# FULL_CB_80_Pin_REV_C.net
KiCad netlist of a schematic drawn in Altium Designer
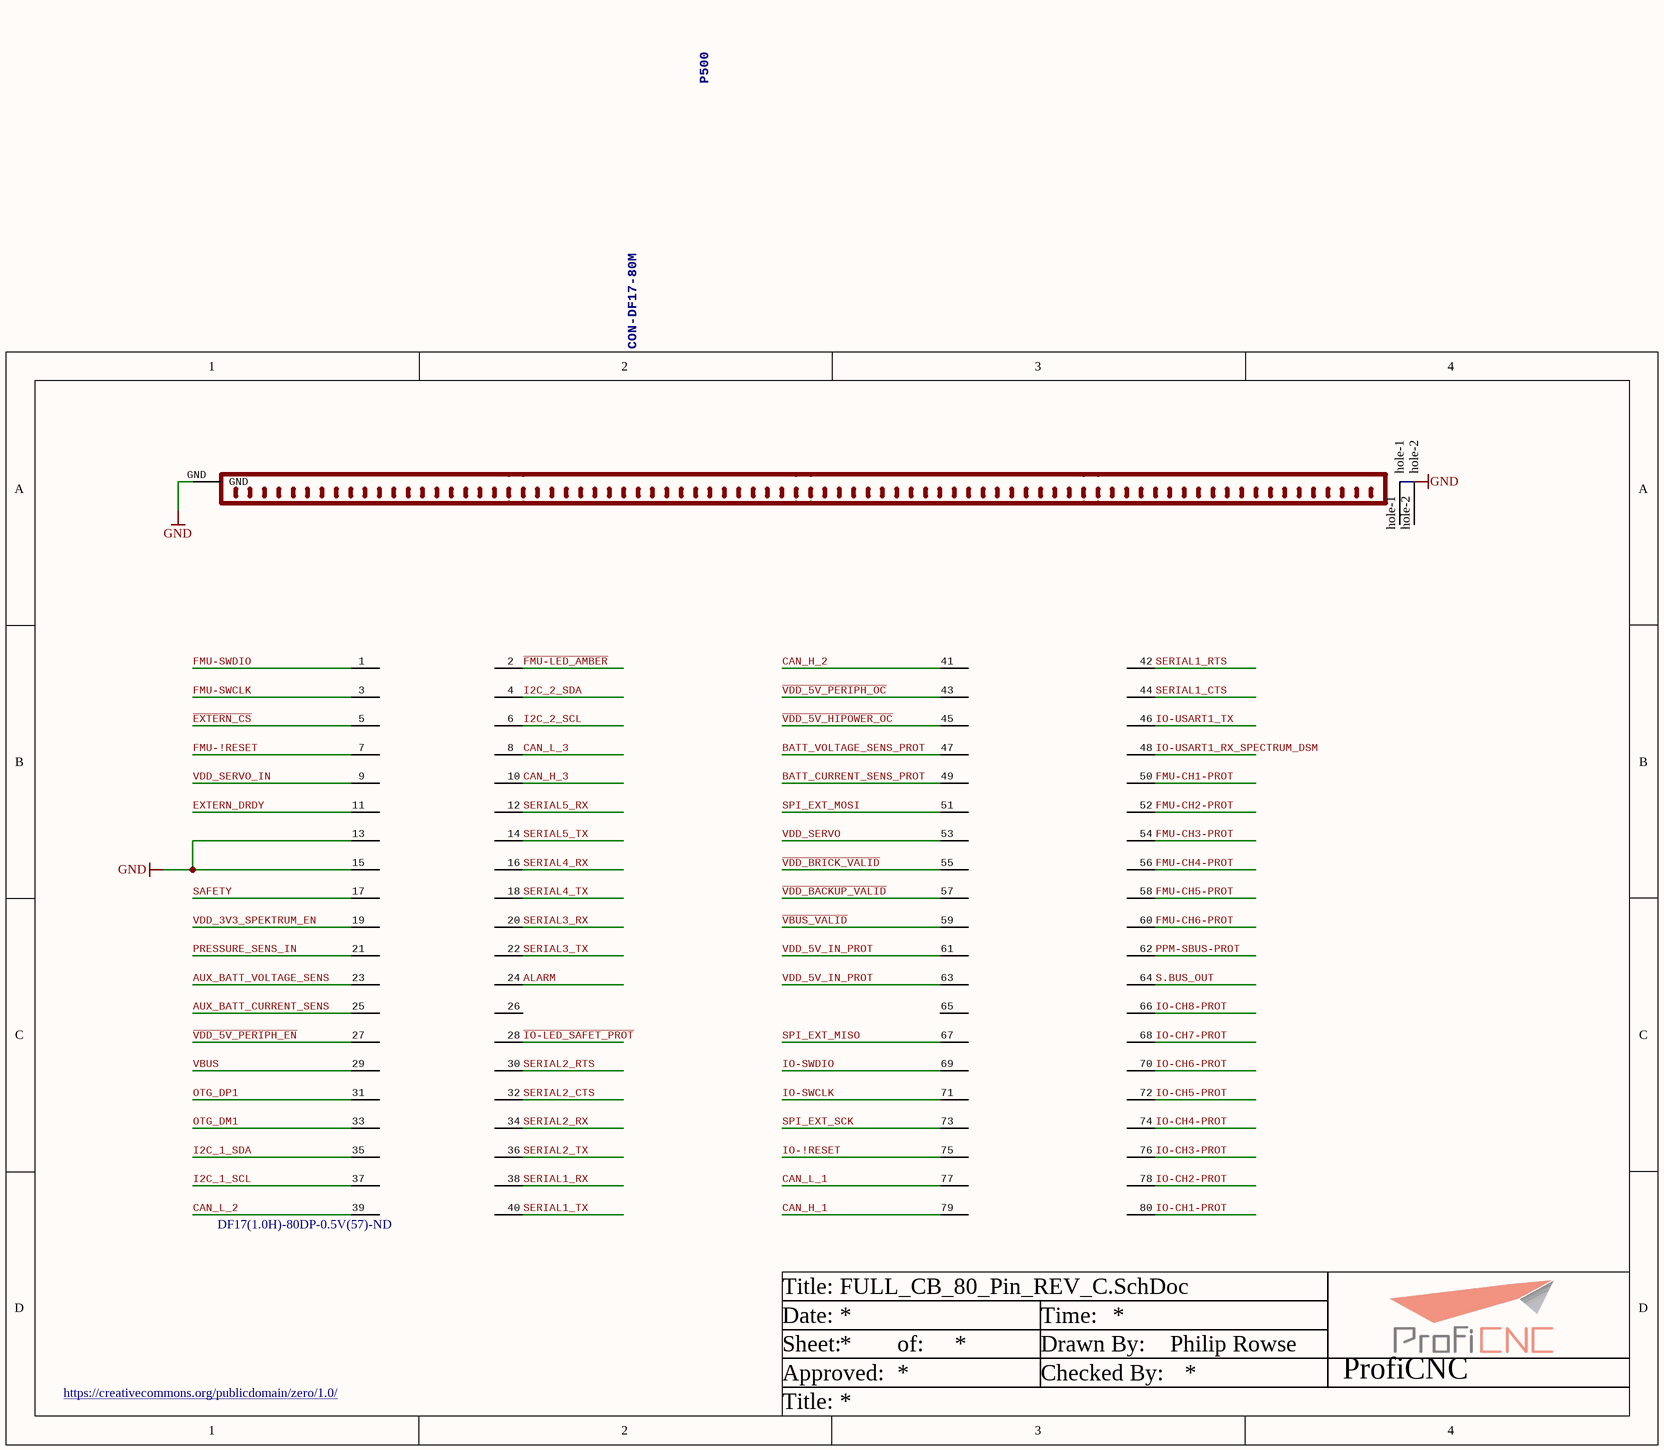
[diagram p0: FULL_CB_80_Pin_REV_C.SchDoc]

(export (version "E")
  (design (tool "Eeschema 10.0.6"))
  (components
    (comp (ref "P500")
      (value "CON-DF17-80M")
      (description "Connector, Header, 80Pos, .5MM, DUAL, SMD, Au")
      (fields (field (name "SUPPLIER PART NUMBER 1") "DF17(1.0H)-80DP-0.5V(57)-ND"))
      (libsource (lib "CB_REV_C") (part "CON-DF17-80M"))
    )
  )
  (nets
    (net (code "1") (name "/ALARM") (class "Default")
      (node (ref "P500") (pin "24") (pinfunction "24_24") (pintype "passive"))
    )
    (net (code "2") (name "/AUX_BATT_CURRENT_SENS") (class "Default")
      (node (ref "P500") (pin "25") (pinfunction "25_25") (pintype "passive"))
    )
    (net (code "3") (name "/AUX_BATT_VOLTAGE_SENS") (class "Default")
      (node (ref "P500") (pin "23") (pinfunction "23_23") (pintype "passive"))
    )
    (net (code "4") (name "/BATT_CURRENT_SENS_PROT") (class "Default")
      (node (ref "P500") (pin "49") (pinfunction "49_49") (pintype "passive"))
    )
    (net (code "5") (name "/BATT_VOLTAGE_SENS_PROT") (class "Default")
      (node (ref "P500") (pin "47") (pinfunction "47_47") (pintype "passive"))
    )
    (net (code "6") (name "/CAN_H_1") (class "Default")
      (node (ref "P500") (pin "79") (pinfunction "79_79") (pintype "passive"))
    )
    (net (code "7") (name "/CAN_H_2") (class "Default")
      (node (ref "P500") (pin "41") (pinfunction "41_41") (pintype "passive"))
    )
    (net (code "8") (name "/CAN_H_3") (class "Default")
      (node (ref "P500") (pin "10") (pinfunction "10_10") (pintype "passive"))
    )
    (net (code "9") (name "/CAN_L_1") (class "Default")
      (node (ref "P500") (pin "77") (pinfunction "77_77") (pintype "passive"))
    )
    (net (code "10") (name "/CAN_L_2") (class "Default")
      (node (ref "P500") (pin "39") (pinfunction "39_39") (pintype "passive"))
    )
    (net (code "11") (name "/CAN_L_3") (class "Default")
      (node (ref "P500") (pin "8") (pinfunction "8_8") (pintype "passive"))
    )
    (net (code "12") (name "/EXTERN_DRDY") (class "Default")
      (node (ref "P500") (pin "11") (pinfunction "11_11") (pintype "passive"))
    )
    (net (code "13") (name "/FMU-!RESET") (class "Default")
      (node (ref "P500") (pin "7") (pinfunction "7_7") (pintype "passive"))
    )
    (net (code "14") (name "/FMU-CH1-PROT") (class "Default")
      (node (ref "P500") (pin "50") (pinfunction "50_50") (pintype "passive"))
    )
    (net (code "15") (name "/FMU-CH2-PROT") (class "Default")
      (node (ref "P500") (pin "52") (pinfunction "52_52") (pintype "passive"))
    )
    (net (code "16") (name "/FMU-CH3-PROT") (class "Default")
      (node (ref "P500") (pin "54") (pinfunction "54_54") (pintype "passive"))
    )
    (net (code "17") (name "/FMU-CH4-PROT") (class "Default")
      (node (ref "P500") (pin "56") (pinfunction "56_56") (pintype "passive"))
    )
    (net (code "18") (name "/FMU-CH5-PROT") (class "Default")
      (node (ref "P500") (pin "58") (pinfunction "58_58") (pintype "passive"))
    )
    (net (code "19") (name "/FMU-CH6-PROT") (class "Default")
      (node (ref "P500") (pin "60") (pinfunction "60_60") (pintype "passive"))
    )
    (net (code "20") (name "/FMU-SWCLK") (class "Default")
      (node (ref "P500") (pin "3") (pinfunction "3_3") (pintype "passive"))
    )
    (net (code "21") (name "/FMU-SWDIO") (class "Default")
      (node (ref "P500") (pin "1") (pinfunction "1_1") (pintype "passive"))
    )
    (net (code "22") (name "/I2C_1_SCL") (class "Default")
      (node (ref "P500") (pin "37") (pinfunction "37_37") (pintype "passive"))
    )
    (net (code "23") (name "/I2C_1_SDA") (class "Default")
      (node (ref "P500") (pin "35") (pinfunction "35_35") (pintype "passive"))
    )
    (net (code "24") (name "/I2C_2_SCL") (class "Default")
      (node (ref "P500") (pin "6") (pinfunction "6_6") (pintype "passive"))
    )
    (net (code "25") (name "/I2C_2_SDA") (class "Default")
      (node (ref "P500") (pin "4") (pinfunction "4_4") (pintype "passive"))
    )
    (net (code "26") (name "/IO-!RESET") (class "Default")
      (node (ref "P500") (pin "75") (pinfunction "75_75") (pintype "passive"))
    )
    (net (code "27") (name "/IO-CH1-PROT") (class "Default")
      (node (ref "P500") (pin "80") (pinfunction "80_80") (pintype "passive"))
    )
    (net (code "28") (name "/IO-CH2-PROT") (class "Default")
      (node (ref "P500") (pin "78") (pinfunction "78_78") (pintype "passive"))
    )
    (net (code "29") (name "/IO-CH3-PROT") (class "Default")
      (node (ref "P500") (pin "76") (pinfunction "76_76") (pintype "passive"))
    )
    (net (code "30") (name "/IO-CH4-PROT") (class "Default")
      (node (ref "P500") (pin "74") (pinfunction "74_74") (pintype "passive"))
    )
    (net (code "31") (name "/IO-CH5-PROT") (class "Default")
      (node (ref "P500") (pin "72") (pinfunction "72_72") (pintype "passive"))
    )
    (net (code "32") (name "/IO-CH6-PROT") (class "Default")
      (node (ref "P500") (pin "70") (pinfunction "70_70") (pintype "passive"))
    )
    (net (code "33") (name "/IO-CH7-PROT") (class "Default")
      (node (ref "P500") (pin "68") (pinfunction "68_68") (pintype "passive"))
    )
    (net (code "34") (name "/IO-CH8-PROT") (class "Default")
      (node (ref "P500") (pin "66") (pinfunction "66_66") (pintype "passive"))
    )
    (net (code "35") (name "/IO-SWCLK") (class "Default")
      (node (ref "P500") (pin "71") (pinfunction "71_71") (pintype "passive"))
    )
    (net (code "36") (name "/IO-SWDIO") (class "Default")
      (node (ref "P500") (pin "69") (pinfunction "69_69") (pintype "passive"))
    )
    (net (code "37") (name "/IO-USART1_RX_SPECTRUM_DSM") (class "Default")
      (node (ref "P500") (pin "48") (pinfunction "48_48") (pintype "passive"))
    )
    (net (code "38") (name "/IO-USART1_TX") (class "Default")
      (node (ref "P500") (pin "46") (pinfunction "46_46") (pintype "passive"))
    )
    (net (code "39") (name "/OTG_DM1") (class "Default")
      (node (ref "P500") (pin "33") (pinfunction "33_33") (pintype "passive"))
    )
    (net (code "40") (name "/OTG_DP1") (class "Default")
      (node (ref "P500") (pin "31") (pinfunction "31_31") (pintype "passive"))
    )
    (net (code "41") (name "/PPM-SBUS-PROT") (class "Default")
      (node (ref "P500") (pin "62") (pinfunction "62_62") (pintype "passive"))
    )
    (net (code "42") (name "/PRESSURE_SENS_IN") (class "Default")
      (node (ref "P500") (pin "21") (pinfunction "21_21") (pintype "passive"))
    )
    (net (code "43") (name "/S.BUS_OUT") (class "Default")
      (node (ref "P500") (pin "64") (pinfunction "64_64") (pintype "passive"))
    )
    (net (code "44") (name "/SAFETY") (class "Default")
      (node (ref "P500") (pin "17") (pinfunction "17_17") (pintype "passive"))
    )
    (net (code "45") (name "/SERIAL1_CTS") (class "Default")
      (node (ref "P500") (pin "44") (pinfunction "44_44") (pintype "passive"))
    )
    (net (code "46") (name "/SERIAL1_RTS") (class "Default")
      (node (ref "P500") (pin "42") (pinfunction "42_42") (pintype "passive"))
    )
    (net (code "47") (name "/SERIAL1_RX") (class "Default")
      (node (ref "P500") (pin "38") (pinfunction "38_38") (pintype "passive"))
    )
    (net (code "48") (name "/SERIAL1_TX") (class "Default")
      (node (ref "P500") (pin "40") (pinfunction "40_40") (pintype "passive"))
    )
    (net (code "49") (name "/SERIAL2_CTS") (class "Default")
      (node (ref "P500") (pin "32") (pinfunction "32_32") (pintype "passive"))
    )
    (net (code "50") (name "/SERIAL2_RTS") (class "Default")
      (node (ref "P500") (pin "30") (pinfunction "30_30") (pintype "passive"))
    )
    (net (code "51") (name "/SERIAL2_RX") (class "Default")
      (node (ref "P500") (pin "34") (pinfunction "34_34") (pintype "passive"))
    )
    (net (code "52") (name "/SERIAL2_TX") (class "Default")
      (node (ref "P500") (pin "36") (pinfunction "36_36") (pintype "passive"))
    )
    (net (code "53") (name "/SERIAL3_RX") (class "Default")
      (node (ref "P500") (pin "20") (pinfunction "20_20") (pintype "passive"))
    )
    (net (code "54") (name "/SERIAL3_TX") (class "Default")
      (node (ref "P500") (pin "22") (pinfunction "22_22") (pintype "passive"))
    )
    (net (code "55") (name "/SERIAL4_RX") (class "Default")
      (node (ref "P500") (pin "16") (pinfunction "16_16") (pintype "passive"))
    )
    (net (code "56") (name "/SERIAL4_TX") (class "Default")
      (node (ref "P500") (pin "18") (pinfunction "18_18") (pintype "passive"))
    )
    (net (code "57") (name "/SERIAL5_RX") (class "Default")
      (node (ref "P500") (pin "12") (pinfunction "12_12") (pintype "passive"))
    )
    (net (code "58") (name "/SERIAL5_TX") (class "Default")
      (node (ref "P500") (pin "14") (pinfunction "14_14") (pintype "passive"))
    )
    (net (code "59") (name "/SPI_EXT_MISO") (class "Default")
      (node (ref "P500") (pin "67") (pinfunction "67_67") (pintype "passive"))
    )
    (net (code "60") (name "/SPI_EXT_MOSI") (class "Default")
      (node (ref "P500") (pin "51") (pinfunction "51_51") (pintype "passive"))
    )
    (net (code "61") (name "/SPI_EXT_SCK") (class "Default")
      (node (ref "P500") (pin "73") (pinfunction "73_73") (pintype "passive"))
    )
    (net (code "62") (name "/VBUS") (class "Default")
      (node (ref "P500") (pin "29") (pinfunction "29_29") (pintype "passive"))
    )
    (net (code "63") (name "/VDD_3V3_SPEKTRUM_EN") (class "Default")
      (node (ref "P500") (pin "19") (pinfunction "19_19") (pintype "passive"))
    )
    (net (code "64") (name "/VDD_5V_IN_PROT") (class "Default")
      (node (ref "P500") (pin "61") (pinfunction "61_61") (pintype "passive"))
      (node (ref "P500") (pin "63") (pinfunction "63_63") (pintype "passive"))
    )
    (net (code "65") (name "/VDD_SERVO") (class "Default")
      (node (ref "P500") (pin "53") (pinfunction "53_53") (pintype "passive"))
    )
    (net (code "66") (name "/VDD_SERVO_IN") (class "Default")
      (node (ref "P500") (pin "9") (pinfunction "9_9") (pintype "passive"))
    )
    (net (code "67") (name "/~{EXTERN_CS}") (class "Default")
      (node (ref "P500") (pin "5") (pinfunction "5_5") (pintype "passive"))
    )
    (net (code "68") (name "/~{FMU-LED_AMBER}") (class "Default")
      (node (ref "P500") (pin "2") (pinfunction "2_2") (pintype "passive"))
    )
    (net (code "69") (name "/~{IO-LED_SAFET_PROT}") (class "Default")
      (node (ref "P500") (pin "28") (pinfunction "28_28") (pintype "passive"))
    )
    (net (code "70") (name "/~{VBUS_VALID}") (class "Default")
      (node (ref "P500") (pin "59") (pinfunction "59_59") (pintype "passive"))
    )
    (net (code "71") (name "/~{VDD_5V_HIPOWER_OC}") (class "Default")
      (node (ref "P500") (pin "45") (pinfunction "45_45") (pintype "passive"))
    )
    (net (code "72") (name "/~{VDD_5V_PERIPH_EN}") (class "Default")
      (node (ref "P500") (pin "27") (pinfunction "27_27") (pintype "passive"))
    )
    (net (code "73") (name "/~{VDD_5V_PERIPH_OC}") (class "Default")
      (node (ref "P500") (pin "43") (pinfunction "43_43") (pintype "passive"))
    )
    (net (code "74") (name "/~{VDD_BACKUP_VALID}") (class "Default")
      (node (ref "P500") (pin "57") (pinfunction "57_57") (pintype "passive"))
    )
    (net (code "75") (name "/~{VDD_BRICK_VALID}") (class "Default")
      (node (ref "P500") (pin "55") (pinfunction "55_55") (pintype "passive"))
    )
    (net (code "76") (name "GND") (class "Default")
      (node (ref "P500") (pin "13") (pinfunction "13_13") (pintype "passive"))
      (node (ref "P500") (pin "15") (pinfunction "15_15") (pintype "passive"))
      (node (ref "P500") (pin "GND") (pinfunction "GND_GND") (pintype "passive"))
    )
    (net (code "77") (name "unconnected-(P500-Pad26)") (class "Default")
      (node (ref "P500") (pin "26") (pinfunction "26_26") (pintype "passive"))
    )
    (net (code "78") (name "unconnected-(P500-Pad65)") (class "Default")
      (node (ref "P500") (pin "65") (pinfunction "65_65") (pintype "passive"))
    )
    (net (code "79") (name "unconnected-(P500-Padhole-1)") (class "Default")
      (node (ref "P500") (pin "hole-1") (pinfunction "hole-1_hole-1") (pintype "passive"))
    )
    (net (code "80") (name "unconnected-(P500-Padhole-2)") (class "Default")
      (node (ref "P500") (pin "hole-2") (pinfunction "hole-2_hole-2") (pintype "passive"))
    )
  )
)
